# holo_control.net
KiCad netlist of a schematic drawn in EAGLE
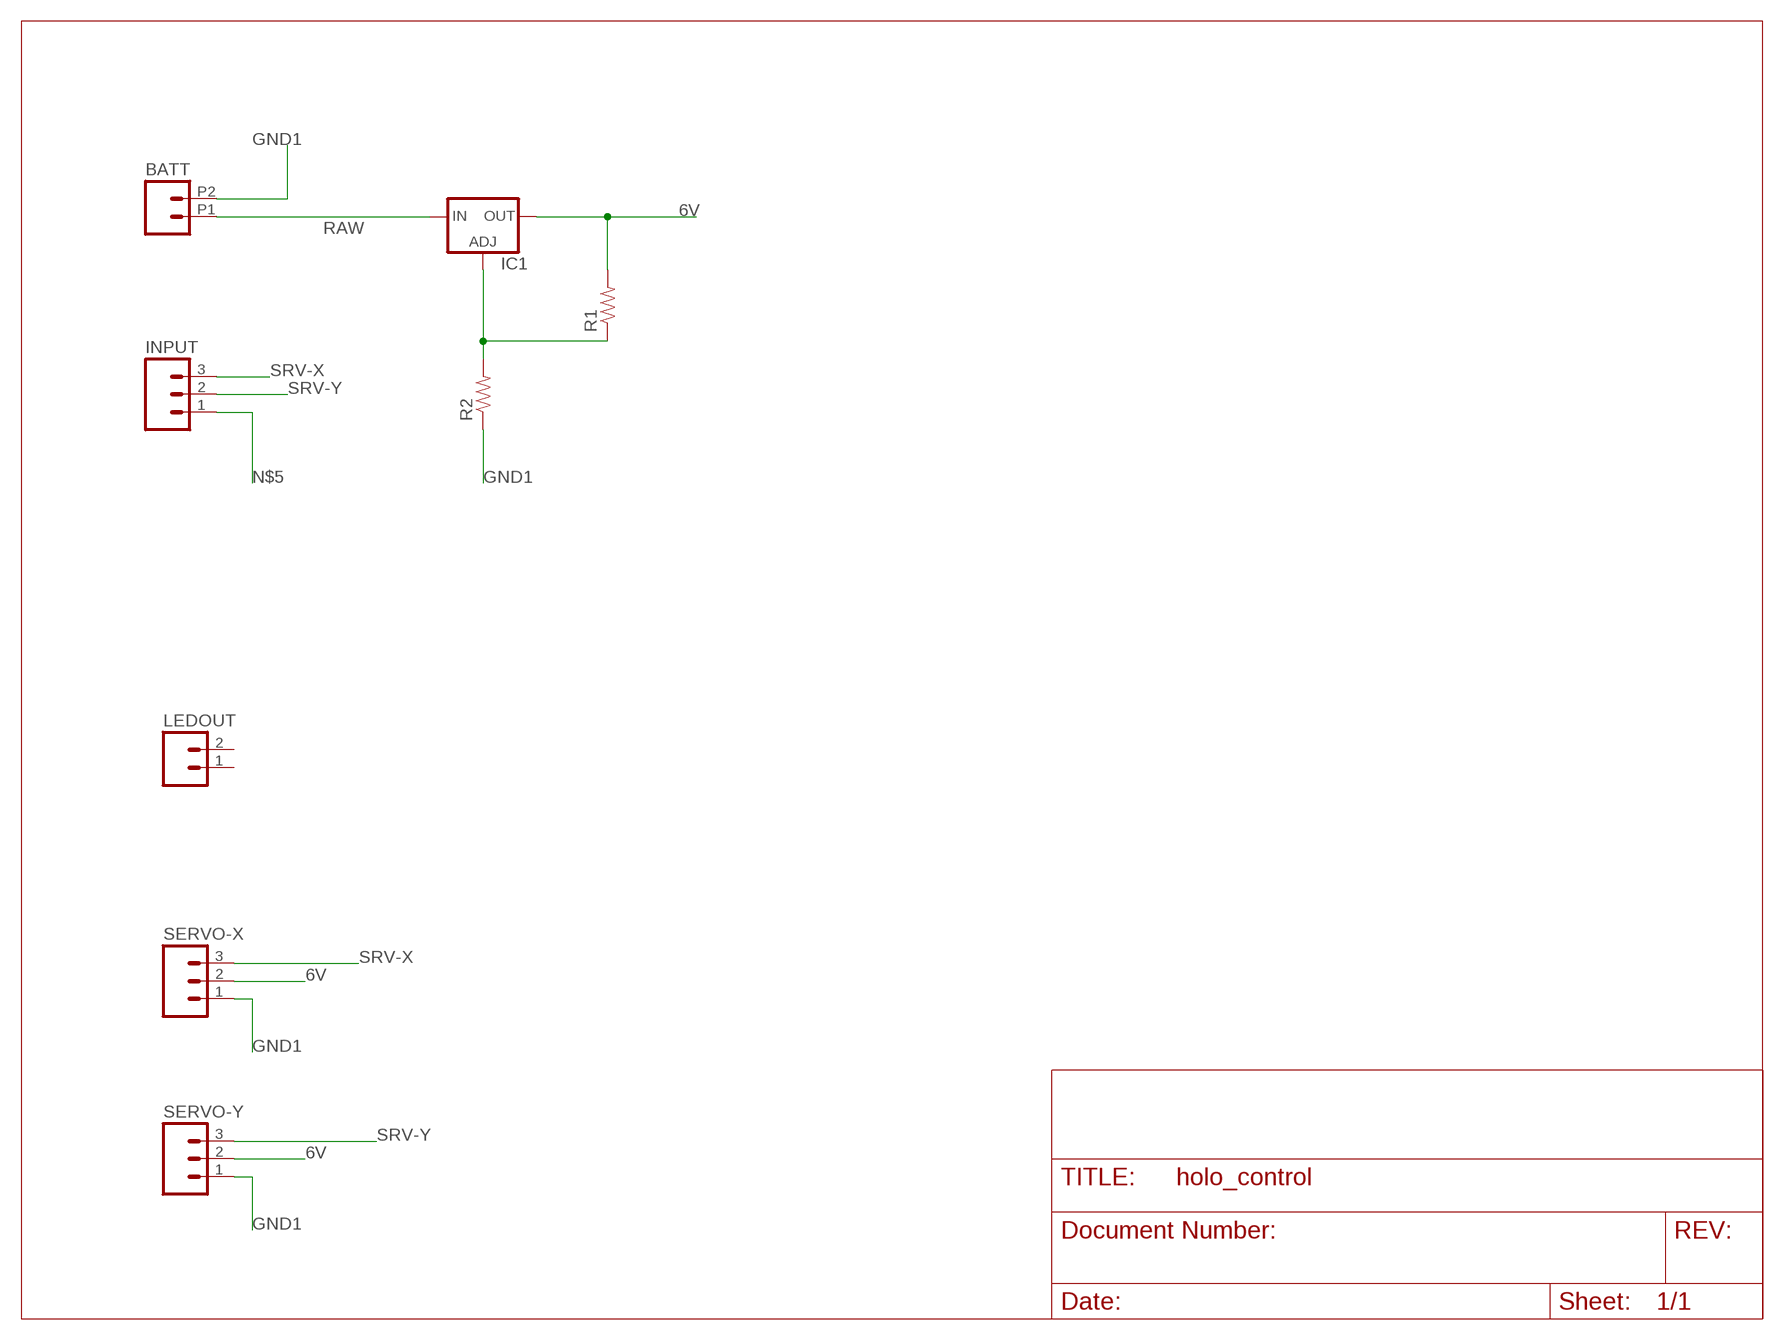
[diagram p0: schematic, sheet 1]

(export (version "E")
  (design (tool "Eeschema 10.0.6"))
  (components
    (comp (ref "BATT")
      (value "M022.54MM_SCREWTERM")
      (footprint "eagle-import:1X02_2.54_SCREWTERM")
      (libsource (lib "eagle-import") (part "M022.54MM_SCREWTERM"))
    )
    (comp (ref "IC1")
      (value "LM317TS")
      (footprint "eagle-import:317TS")
      (libsource (lib "eagle-import") (part "LM317TS"))
    )
    (comp (ref "INPUT")
      (value "M03PTH")
      (footprint "eagle-import:1X03")
      (libsource (lib "eagle-import") (part "M03PTH"))
    )
    (comp (ref "LEDOUT")
      (value "M02PTH")
      (footprint "eagle-import:1X02")
      (libsource (lib "eagle-import") (part "M02PTH"))
    )
    (comp (ref "R1")
      (value "RESISTORPTH-1/4W")
      (footprint "eagle-import:AXIAL-0.4")
      (libsource (lib "eagle-import") (part "RESISTORPTH-1/4W"))
    )
    (comp (ref "R2")
      (value "RESISTORPTH-1/4W")
      (footprint "eagle-import:AXIAL-0.4")
      (libsource (lib "eagle-import") (part "RESISTORPTH-1/4W"))
    )
    (comp (ref "SERVO-X")
      (value "M03PTH")
      (footprint "eagle-import:1X03")
      (libsource (lib "eagle-import") (part "M03PTH"))
    )
    (comp (ref "SERVO-Y")
      (value "M03PTH")
      (footprint "eagle-import:1X03")
      (libsource (lib "eagle-import") (part "M03PTH"))
    )
  )
  (nets
    (net (code "1") (name "/6V") (class "Default")
      (node (ref "IC1") (pin "2") (pinfunction "OUT_2") (pintype "passive"))
      (node (ref "R1") (pin "P$2") (pinfunction "2_P$2") (pintype "passive"))
      (node (ref "SERVO-X") (pin "2") (pinfunction "2_2") (pintype "passive"))
      (node (ref "SERVO-Y") (pin "2") (pinfunction "2_2") (pintype "passive"))
    )
    (net (code "2") (name "/GND1") (class "Default")
      (node (ref "BATT") (pin "P2") (pinfunction "2_P2") (pintype "passive"))
      (node (ref "R2") (pin "P$1") (pinfunction "1_P$1") (pintype "passive"))
      (node (ref "SERVO-X") (pin "1") (pinfunction "1_1") (pintype "passive"))
      (node (ref "SERVO-Y") (pin "1") (pinfunction "1_1") (pintype "passive"))
    )
    (net (code "3") (name "/N$5") (class "Default")
      (node (ref "INPUT") (pin "1") (pinfunction "1_1") (pintype "passive"))
    )
    (net (code "4") (name "/RAW") (class "Default")
      (node (ref "BATT") (pin "P1") (pinfunction "1_P1") (pintype "passive"))
      (node (ref "IC1") (pin "3") (pinfunction "IN_3") (pintype "input"))
    )
    (net (code "5") (name "/SRV-X") (class "Default")
      (node (ref "INPUT") (pin "3") (pinfunction "3_3") (pintype "passive"))
      (node (ref "SERVO-X") (pin "3") (pinfunction "3_3") (pintype "passive"))
    )
    (net (code "6") (name "/SRV-Y") (class "Default")
      (node (ref "INPUT") (pin "2") (pinfunction "2_2") (pintype "passive"))
      (node (ref "SERVO-Y") (pin "3") (pinfunction "3_3") (pintype "passive"))
    )
    (net (code "7") (name "Net-(IC1-ADJ)") (class "Default")
      (node (ref "IC1") (pin "1") (pinfunction "ADJ_1") (pintype "input"))
      (node (ref "R1") (pin "P$1") (pinfunction "1_P$1") (pintype "passive"))
      (node (ref "R2") (pin "P$2") (pinfunction "2_P$2") (pintype "passive"))
    )
    (net (code "8") (name "unconnected-(LEDOUT-Pad1)") (class "Default")
      (node (ref "LEDOUT") (pin "1") (pinfunction "1_1") (pintype "passive"))
    )
    (net (code "9") (name "unconnected-(LEDOUT-Pad2)") (class "Default")
      (node (ref "LEDOUT") (pin "2") (pinfunction "2_2") (pintype "passive"))
    )
  )
)
